# flipflop-jk-edgetrigger.net
KiCad netlist of a schematic drawn in EAGLE
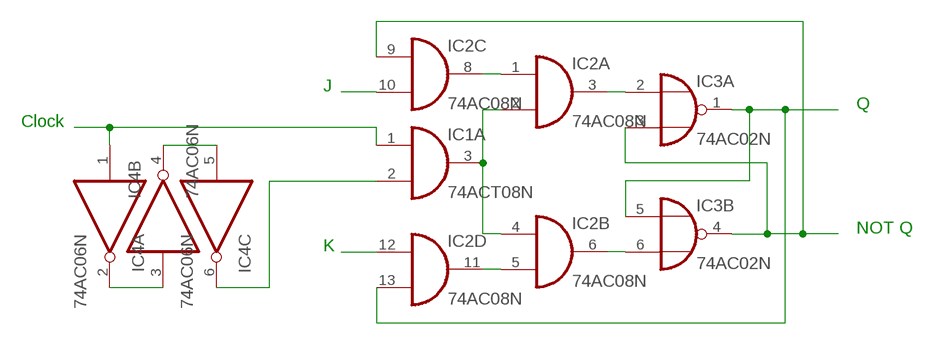
[diagram p0: schematic, sheet 1]

(export (version "E")
  (design (tool "Eeschema 10.0.6"))
  (components
    (comp (ref "IC1")
      (value "74ACT08N")
      (footprint "eagle-import:DIL14")
      (libsource (lib "eagle-import") (part "7408NACT"))
    )
    (comp (ref "IC2")
      (value "74AC08N")
      (footprint "eagle-import:DIL14")
      (libsource (lib "eagle-import") (part "7408NAC"))
    )
    (comp (ref "IC3")
      (value "74AC02N")
      (footprint "eagle-import:DIL14")
      (libsource (lib "eagle-import") (part "7402NAC"))
    )
    (comp (ref "IC4")
      (value "74AC06N")
      (footprint "eagle-import:DIL14")
      (libsource (lib "eagle-import") (part "7406NAC"))
    )
  )
  (nets
    (net (code "1") (name "Net-(IC1A-I0)") (class "Default")
      (node (ref "IC1") (pin "1") (pinfunction "I0_1") (pintype "input"))
      (node (ref "IC4") (pin "1") (pinfunction "I_1") (pintype "input"))
    )
    (net (code "2") (name "Net-(IC1A-I1)") (class "Default")
      (node (ref "IC1") (pin "2") (pinfunction "I1_2") (pintype "input"))
      (node (ref "IC4") (pin "6") (pinfunction "O_6") (pintype "open_collector"))
    )
    (net (code "3") (name "Net-(IC1A-O)") (class "Default")
      (node (ref "IC1") (pin "3") (pinfunction "O_3") (pintype "output"))
      (node (ref "IC2") (pin "2") (pinfunction "I1_2") (pintype "input"))
      (node (ref "IC2") (pin "4") (pinfunction "I0_4") (pintype "input"))
    )
    (net (code "4") (name "Net-(IC2A-I0)") (class "Default")
      (node (ref "IC2") (pin "1") (pinfunction "I0_1") (pintype "input"))
      (node (ref "IC2") (pin "8") (pinfunction "O_8") (pintype "output"))
    )
    (net (code "5") (name "Net-(IC2A-O)") (class "Default")
      (node (ref "IC2") (pin "3") (pinfunction "O_3") (pintype "output"))
      (node (ref "IC3") (pin "2") (pinfunction "I0_2") (pintype "input"))
    )
    (net (code "6") (name "Net-(IC2B-I1)") (class "Default")
      (node (ref "IC2") (pin "11") (pinfunction "O_11") (pintype "output"))
      (node (ref "IC2") (pin "5") (pinfunction "I1_5") (pintype "input"))
    )
    (net (code "7") (name "Net-(IC2B-O)") (class "Default")
      (node (ref "IC2") (pin "6") (pinfunction "O_6") (pintype "output"))
      (node (ref "IC3") (pin "6") (pinfunction "I1_6") (pintype "input"))
    )
    (net (code "8") (name "Net-(IC2C-I0)") (class "Default")
      (node (ref "IC2") (pin "9") (pinfunction "I0_9") (pintype "input"))
      (node (ref "IC3") (pin "3") (pinfunction "I1_3") (pintype "input"))
      (node (ref "IC3") (pin "4") (pinfunction "O_4") (pintype "output"))
    )
    (net (code "9") (name "Net-(IC2D-I1)") (class "Default")
      (node (ref "IC2") (pin "13") (pinfunction "I1_13") (pintype "input"))
      (node (ref "IC3") (pin "1") (pinfunction "O_1") (pintype "output"))
      (node (ref "IC3") (pin "5") (pinfunction "I0_5") (pintype "input"))
    )
    (net (code "10") (name "Net-(IC4A-O)") (class "Default")
      (node (ref "IC4") (pin "2") (pinfunction "O_2") (pintype "open_collector"))
      (node (ref "IC4") (pin "3") (pinfunction "I_3") (pintype "input"))
    )
    (net (code "11") (name "Net-(IC4B-O)") (class "Default")
      (node (ref "IC4") (pin "4") (pinfunction "O_4") (pintype "open_collector"))
      (node (ref "IC4") (pin "5") (pinfunction "I_5") (pintype "input"))
    )
    (net (code "12") (name "unconnected-(IC2C-I1-Pad10)") (class "Default")
      (node (ref "IC2") (pin "10") (pinfunction "I1_10") (pintype "input"))
    )
    (net (code "13") (name "unconnected-(IC2D-I0-Pad12)") (class "Default")
      (node (ref "IC2") (pin "12") (pinfunction "I0_12") (pintype "input"))
    )
  )
)
